# P04_Power_Supply1.net
KiCad netlist of a schematic drawn in Altium Designer
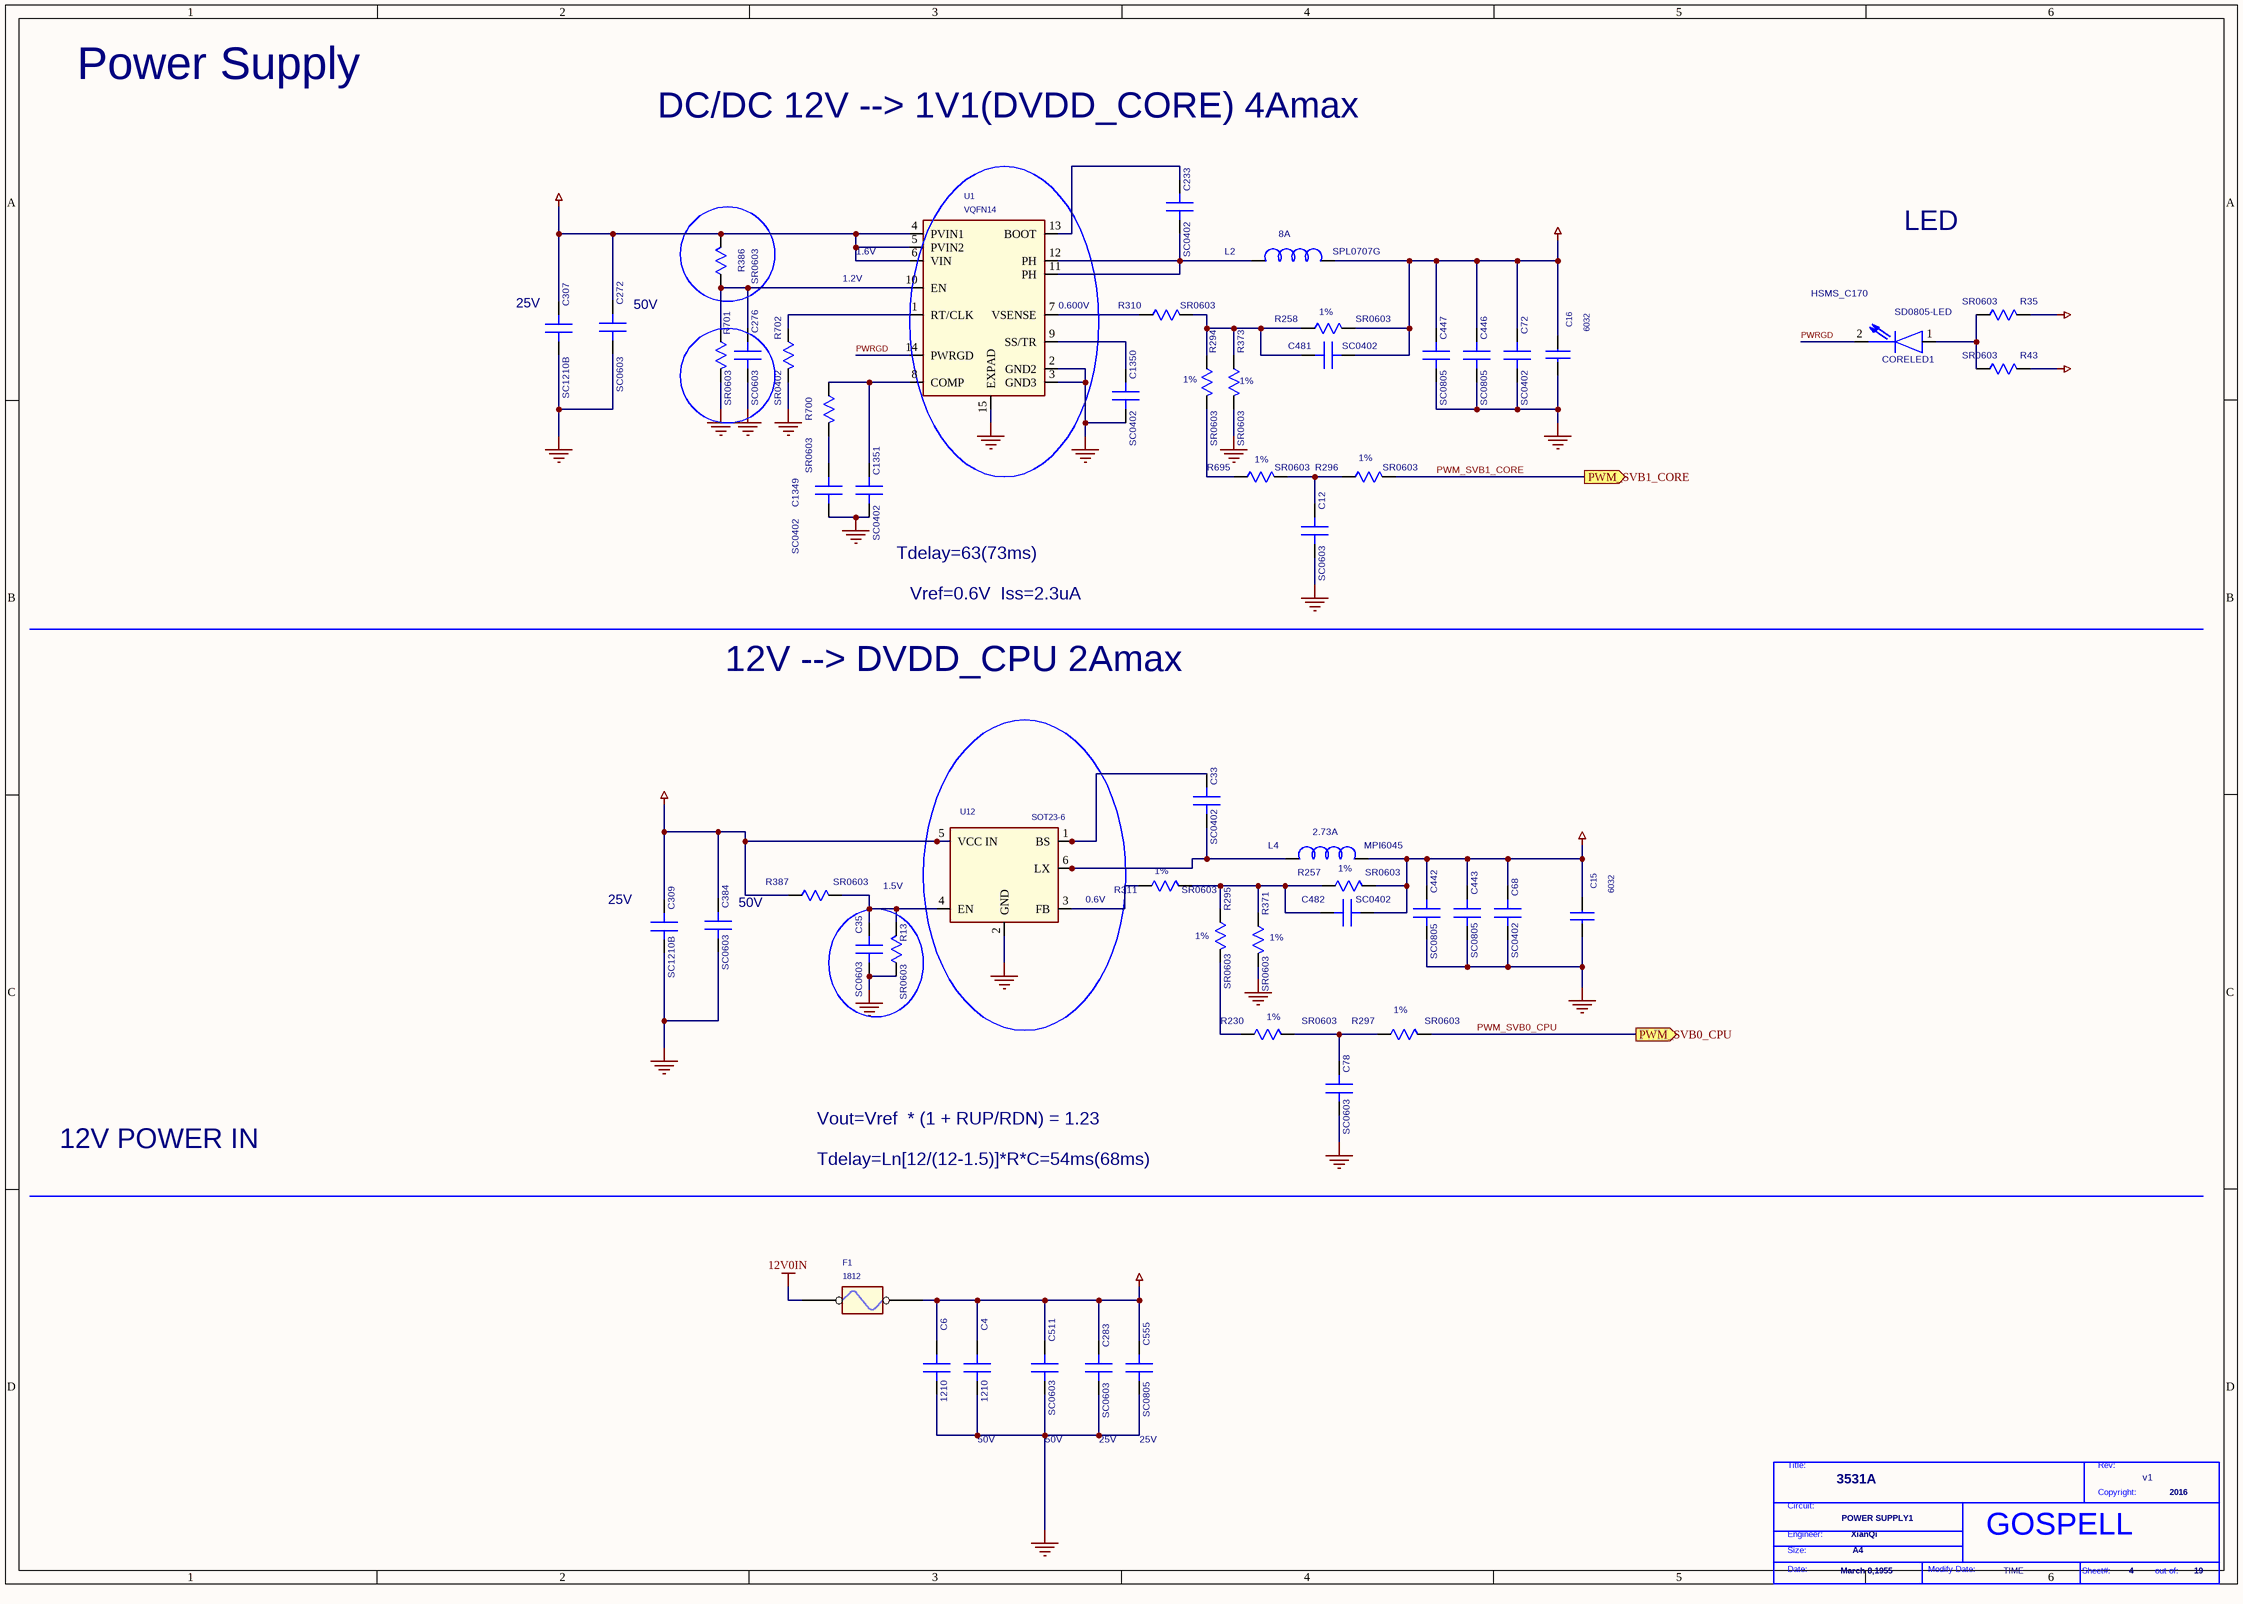
[diagram p0: P04 Power Supply1.SchDoc]

(export (version "E")
  (design (tool "Eeschema 10.0.6"))
  (components
    (comp (ref "C4") (value "1210") (footprint "1210") (libsource (lib "*") (part "C_0_Dup2")))
    (comp (ref "C6") (value "1210") (footprint "1210") (libsource (lib "*") (part "C_0_Dup2")))
    (comp (ref "C12") (value "SC0603") (libsource (lib "*") (part "C_0")))
    (comp (ref "C15") (value "6032") (footprint "6032") (libsource (lib "*") (part "CAP NP")))
    (comp (ref "C16") (value "6032") (footprint "6032") (libsource (lib "*") (part "CAP NP")))
    (comp (ref "C33") (value "SC0402") (libsource (lib "*") (part "C_0_Dup2")))
    (comp (ref "C35") (value "SC0603") (libsource (lib "*") (part "C_0_Dup2")))
    (comp (ref "C68") (value "SC0402") (libsource (lib "*") (part "C_0_Dup2")))
    (comp (ref "C72") (value "SC0402") (libsource (lib "*") (part "C_0")))
    (comp (ref "C78") (value "SC0603") (libsource (lib "*") (part "C_0_Dup2")))
    (comp (ref "C233") (value "SC0402") (libsource (lib "*") (part "C_0")))
    (comp (ref "C272") (value "SC0603") (libsource (lib "*") (part "C_0")))
    (comp (ref "C276") (value "SC0603") (libsource (lib "*") (part "C_0")))
    (comp (ref "C283") (value "SC0603") (libsource (lib "*") (part "C_0_Dup2")))
    (comp (ref "C307") (value "SC1210B") (libsource (lib "*") (part "C_0")))
    (comp (ref "C309") (value "SC1210B") (libsource (lib "*") (part "C_0_Dup2")))
    (comp (ref "C384") (value "SC0603") (libsource (lib "*") (part "C_0_Dup2")))
    (comp (ref "C442") (value "SC0805") (libsource (lib "*") (part "C_0_Dup2")))
    (comp (ref "C443") (value "SC0805") (libsource (lib "*") (part "C_0_Dup2")))
    (comp (ref "C446") (value "SC0805") (libsource (lib "*") (part "C_0")))
    (comp (ref "C447") (value "SC0805") (libsource (lib "*") (part "C_0")))
    (comp (ref "C481") (value "SC0402") (libsource (lib "*") (part "C_0")))
    (comp (ref "C482") (value "SC0402") (libsource (lib "*") (part "C_0_Dup2")))
    (comp (ref "C511") (value "SC0603") (libsource (lib "*") (part "C_0_Dup2")))
    (comp (ref "C555") (value "SC0805") (libsource (lib "*") (part "C_0_Dup2")))
    (comp (ref "C1349") (value "SC0402") (libsource (lib "*") (part "C_0")))
    (comp (ref "C1350") (value "SC0402") (libsource (lib "*") (part "C_0")))
    (comp (ref "C1351") (value "SC0402") (libsource (lib "*") (part "C_0")))
    (comp (ref "CORELED1")
      (value "SD0805-LED")
      (fields (field (name "DEVICE") "HSMS_C170"))
      (libsource (lib "*") (part "LED_1"))
    )
    (comp (ref "F1") (value "1812") (libsource (lib "*") (part "FUSEHOLDER")))
    (comp (ref "L2") (value "SPL0707G") (libsource (lib "*") (part "L_0")))
    (comp (ref "L4") (value "MPI6045") (libsource (lib "*") (part "L_0_Dup1")))
    (comp (ref "R13") (value "SR0603") (libsource (lib "*") (part "R_1")))
    (comp (ref "R35") (value "SR0603") (libsource (lib "*") (part "R_1")))
    (comp (ref "R43") (value "SR0603") (libsource (lib "*") (part "R_1")))
    (comp (ref "R230") (value "SR0603") (libsource (lib "*") (part "R_1")))
    (comp (ref "R257") (value "SR0603") (libsource (lib "*") (part "R_1")))
    (comp (ref "R258") (value "SR0603") (libsource (lib "*") (part "R_0")))
    (comp (ref "R294") (value "SR0603") (libsource (lib "*") (part "R_0")))
    (comp (ref "R295") (value "SR0603") (libsource (lib "*") (part "R_1")))
    (comp (ref "R296") (value "SR0603") (libsource (lib "*") (part "R_0")))
    (comp (ref "R297") (value "SR0603") (libsource (lib "*") (part "R_1")))
    (comp (ref "R310") (value "SR0603") (libsource (lib "*") (part "R_0")))
    (comp (ref "R311") (value "SR0603") (libsource (lib "*") (part "R_1")))
    (comp (ref "R371") (value "SR0603") (libsource (lib "*") (part "R_1")))
    (comp (ref "R373") (value "SR0603") (libsource (lib "*") (part "R_0")))
    (comp (ref "R386") (value "SR0603") (libsource (lib "*") (part "R_0")))
    (comp (ref "R387") (value "SR0603") (libsource (lib "*") (part "R_1")))
    (comp (ref "R695") (value "SR0603") (libsource (lib "*") (part "R_0")))
    (comp (ref "R700") (value "SR0603") (libsource (lib "*") (part "R_0")))
    (comp (ref "R701") (value "SR0603") (libsource (lib "*") (part "R_0")))
    (comp (ref "R702") (value "SR0402") (libsource (lib "*") (part "R_0")))
    (comp (ref "U1") (value "VQFN14") (footprint "VQFN14") (libsource (lib "*") (part "TPS54821")))
    (comp (ref "U12") (value "SOT23-6") (footprint "SOT23-6") (libsource (lib "*") (part "SY8120")))
  )
  (nets
    (net (code "1") (name "/PWM_SVB0_CPU") (class "Default")
      (node (ref "R297") (pin "2") (pinfunction "B_2") (pintype "passive"))
    )
    (net (code "2") (name "/PWM_SVB1_CORE") (class "Default")
      (node (ref "R296") (pin "2") (pinfunction "B_2") (pintype "passive"))
    )
    (net (code "3") (name "/PWRGD") (class "Default")
      (node (ref "CORELED1") (pin "2") (pinfunction "B_2") (pintype "passive"))
      (node (ref "U1") (pin "14") (pinfunction "PWRGD_14") (pintype "passive"))
    )
    (net (code "4") (name "3V3") (class "Default")
      (node (ref "R35") (pin "1") (pinfunction "A_1") (pintype "passive"))
    )
    (net (code "5") (name "12V0") (class "Default")
      (node (ref "C272") (pin "1") (pinfunction "A_1") (pintype "passive"))
      (node (ref "C283") (pin "1") (pinfunction "A_1") (pintype "passive"))
      (node (ref "C307") (pin "1") (pinfunction "A_1") (pintype "passive"))
      (node (ref "C309") (pin "1") (pinfunction "A_1") (pintype "passive"))
      (node (ref "C384") (pin "1") (pinfunction "A_1") (pintype "passive"))
      (node (ref "C4") (pin "1") (pinfunction "A_1") (pintype "passive"))
      (node (ref "C511") (pin "1") (pinfunction "A_1") (pintype "passive"))
      (node (ref "C555") (pin "1") (pinfunction "A_1") (pintype "passive"))
      (node (ref "C6") (pin "1") (pinfunction "A_1") (pintype "passive"))
      (node (ref "F1") (pin "2") (pinfunction "2_2") (pintype "passive"))
      (node (ref "R386") (pin "2") (pinfunction "B_2") (pintype "passive"))
      (node (ref "R387") (pin "1") (pinfunction "A_1") (pintype "passive"))
      (node (ref "R43") (pin "1") (pinfunction "A_1") (pintype "passive"))
      (node (ref "U1") (pin "4") (pinfunction "PVIN1_4") (pintype "passive"))
      (node (ref "U1") (pin "5") (pinfunction "PVIN2_5") (pintype "passive"))
      (node (ref "U1") (pin "6") (pinfunction "VIN_6") (pintype "passive"))
      (node (ref "U12") (pin "5") (pinfunction "VCC_IN_5") (pintype "passive"))
    )
    (net (code "6") (name "12V0IN") (class "Default")
      (node (ref "F1") (pin "1") (pinfunction "1_1") (pintype "passive"))
    )
    (net (code "7") (name "DVDD_CORE") (class "Default")
      (node (ref "C16") (pin "1") (pinfunction "1_1") (pintype "passive"))
      (node (ref "C446") (pin "1") (pinfunction "A_1") (pintype "passive"))
      (node (ref "C447") (pin "1") (pinfunction "A_1") (pintype "passive"))
      (node (ref "C481") (pin "2") (pinfunction "B_2") (pintype "passive"))
      (node (ref "C72") (pin "1") (pinfunction "A_1") (pintype "passive"))
      (node (ref "L2") (pin "2") (pinfunction "B_2") (pintype "passive"))
      (node (ref "R258") (pin "2") (pinfunction "B_2") (pintype "passive"))
    )
    (net (code "8") (name "DVDD_CPU") (class "Default")
      (node (ref "C15") (pin "1") (pinfunction "1_1") (pintype "passive"))
      (node (ref "C442") (pin "1") (pinfunction "A_1") (pintype "passive"))
      (node (ref "C443") (pin "1") (pinfunction "A_1") (pintype "passive"))
      (node (ref "C482") (pin "2") (pinfunction "B_2") (pintype "passive"))
      (node (ref "C68") (pin "1") (pinfunction "A_1") (pintype "passive"))
      (node (ref "L4") (pin "2") (pinfunction "B_2") (pintype "passive"))
      (node (ref "R257") (pin "2") (pinfunction "B_2") (pintype "passive"))
    )
    (net (code "9") (name "GND") (class "Default")
      (node (ref "C12") (pin "2") (pinfunction "B_2") (pintype "passive"))
      (node (ref "C1349") (pin "2") (pinfunction "B_2") (pintype "passive"))
      (node (ref "C1350") (pin "2") (pinfunction "B_2") (pintype "passive"))
      (node (ref "C1351") (pin "2") (pinfunction "B_2") (pintype "passive"))
      (node (ref "C15") (pin "2") (pinfunction "2_2") (pintype "passive"))
      (node (ref "C16") (pin "2") (pinfunction "2_2") (pintype "passive"))
      (node (ref "C272") (pin "2") (pinfunction "B_2") (pintype "passive"))
      (node (ref "C276") (pin "2") (pinfunction "B_2") (pintype "passive"))
      (node (ref "C283") (pin "2") (pinfunction "B_2") (pintype "passive"))
      (node (ref "C307") (pin "2") (pinfunction "B_2") (pintype "passive"))
      (node (ref "C309") (pin "2") (pinfunction "B_2") (pintype "passive"))
      (node (ref "C35") (pin "2") (pinfunction "B_2") (pintype "passive"))
      (node (ref "C384") (pin "2") (pinfunction "B_2") (pintype "passive"))
      (node (ref "C4") (pin "2") (pinfunction "B_2") (pintype "passive"))
      (node (ref "C442") (pin "2") (pinfunction "B_2") (pintype "passive"))
      (node (ref "C443") (pin "2") (pinfunction "B_2") (pintype "passive"))
      (node (ref "C446") (pin "2") (pinfunction "B_2") (pintype "passive"))
      (node (ref "C447") (pin "2") (pinfunction "B_2") (pintype "passive"))
      (node (ref "C511") (pin "2") (pinfunction "B_2") (pintype "passive"))
      (node (ref "C555") (pin "2") (pinfunction "B_2") (pintype "passive"))
      (node (ref "C6") (pin "2") (pinfunction "B_2") (pintype "passive"))
      (node (ref "C68") (pin "2") (pinfunction "B_2") (pintype "passive"))
      (node (ref "C72") (pin "2") (pinfunction "B_2") (pintype "passive"))
      (node (ref "C78") (pin "2") (pinfunction "B_2") (pintype "passive"))
      (node (ref "R13") (pin "1") (pinfunction "A_1") (pintype "passive"))
      (node (ref "R371") (pin "2") (pinfunction "B_2") (pintype "passive"))
      (node (ref "R373") (pin "2") (pinfunction "B_2") (pintype "passive"))
      (node (ref "R701") (pin "2") (pinfunction "B_2") (pintype "passive"))
      (node (ref "R702") (pin "2") (pinfunction "B_2") (pintype "passive"))
      (node (ref "U1") (pin "15") (pinfunction "EXPAD_15") (pintype "passive"))
      (node (ref "U1") (pin "2") (pinfunction "GND2_2") (pintype "passive"))
      (node (ref "U1") (pin "3") (pinfunction "GND3_3") (pintype "passive"))
      (node (ref "U12") (pin "2") (pinfunction "GND_2") (pintype "passive"))
    )
    (net (code "10") (name "Net-(C12-A)") (class "Default")
      (node (ref "C12") (pin "1") (pinfunction "A_1") (pintype "passive"))
      (node (ref "R296") (pin "1") (pinfunction "A_1") (pintype "passive"))
      (node (ref "R695") (pin "2") (pinfunction "B_2") (pintype "passive"))
    )
    (net (code "11") (name "Net-(C33-A)") (class "Default")
      (node (ref "C33") (pin "1") (pinfunction "A_1") (pintype "passive"))
      (node (ref "U12") (pin "1") (pinfunction "BS_1") (pintype "passive"))
    )
    (net (code "12") (name "Net-(C33-B)") (class "Default")
      (node (ref "C33") (pin "2") (pinfunction "B_2") (pintype "passive"))
      (node (ref "L4") (pin "1") (pinfunction "A_1") (pintype "passive"))
      (node (ref "U12") (pin "6") (pinfunction "LX_6") (pintype "passive"))
    )
    (net (code "13") (name "Net-(C35-A)") (class "Default")
      (node (ref "C35") (pin "1") (pinfunction "A_1") (pintype "passive"))
      (node (ref "R13") (pin "2") (pinfunction "B_2") (pintype "passive"))
      (node (ref "R387") (pin "2") (pinfunction "B_2") (pintype "passive"))
      (node (ref "U12") (pin "4") (pinfunction "EN_4") (pintype "passive"))
    )
    (net (code "14") (name "Net-(C78-A)") (class "Default")
      (node (ref "C78") (pin "1") (pinfunction "A_1") (pintype "passive"))
      (node (ref "R230") (pin "2") (pinfunction "B_2") (pintype "passive"))
      (node (ref "R297") (pin "1") (pinfunction "A_1") (pintype "passive"))
    )
    (net (code "15") (name "Net-(C233-A)") (class "Default")
      (node (ref "C233") (pin "1") (pinfunction "A_1") (pintype "passive"))
      (node (ref "U1") (pin "13") (pinfunction "BOOT_13") (pintype "passive"))
    )
    (net (code "16") (name "Net-(C233-B)") (class "Default")
      (node (ref "C233") (pin "2") (pinfunction "B_2") (pintype "passive"))
      (node (ref "L2") (pin "1") (pinfunction "A_1") (pintype "passive"))
      (node (ref "U1") (pin "11") (pinfunction "PH_11") (pintype "passive"))
      (node (ref "U1") (pin "12") (pinfunction "PH_12") (pintype "passive"))
    )
    (net (code "17") (name "Net-(C276-A)") (class "Default")
      (node (ref "C276") (pin "1") (pinfunction "A_1") (pintype "passive"))
      (node (ref "R386") (pin "1") (pinfunction "A_1") (pintype "passive"))
      (node (ref "R701") (pin "1") (pinfunction "A_1") (pintype "passive"))
      (node (ref "U1") (pin "10") (pinfunction "EN_10") (pintype "passive"))
    )
    (net (code "18") (name "Net-(C481-A)") (class "Default")
      (node (ref "C481") (pin "1") (pinfunction "A_1") (pintype "passive"))
      (node (ref "R258") (pin "1") (pinfunction "A_1") (pintype "passive"))
      (node (ref "R294") (pin "1") (pinfunction "A_1") (pintype "passive"))
      (node (ref "R310") (pin "2") (pinfunction "B_2") (pintype "passive"))
      (node (ref "R373") (pin "1") (pinfunction "A_1") (pintype "passive"))
    )
    (net (code "19") (name "Net-(C482-A)") (class "Default")
      (node (ref "C482") (pin "1") (pinfunction "A_1") (pintype "passive"))
      (node (ref "R257") (pin "1") (pinfunction "A_1") (pintype "passive"))
      (node (ref "R295") (pin "1") (pinfunction "A_1") (pintype "passive"))
      (node (ref "R311") (pin "2") (pinfunction "B_2") (pintype "passive"))
      (node (ref "R371") (pin "1") (pinfunction "A_1") (pintype "passive"))
    )
    (net (code "20") (name "Net-(C1349-A)") (class "Default")
      (node (ref "C1349") (pin "1") (pinfunction "A_1") (pintype "passive"))
      (node (ref "R700") (pin "2") (pinfunction "B_2") (pintype "passive"))
    )
    (net (code "21") (name "Net-(C1350-A)") (class "Default")
      (node (ref "C1350") (pin "1") (pinfunction "A_1") (pintype "passive"))
      (node (ref "U1") (pin "9") (pinfunction "SS/TR_9") (pintype "passive"))
    )
    (net (code "22") (name "Net-(C1351-A)") (class "Default")
      (node (ref "C1351") (pin "1") (pinfunction "A_1") (pintype "passive"))
      (node (ref "R700") (pin "1") (pinfunction "A_1") (pintype "passive"))
      (node (ref "U1") (pin "8") (pinfunction "COMP_8") (pintype "passive"))
    )
    (net (code "23") (name "Net-(CORELED1-A)") (class "Default")
      (node (ref "CORELED1") (pin "1") (pinfunction "A_1") (pintype "passive"))
      (node (ref "R35") (pin "2") (pinfunction "B_2") (pintype "passive"))
      (node (ref "R43") (pin "2") (pinfunction "B_2") (pintype "passive"))
    )
    (net (code "24") (name "Net-(R230-A)") (class "Default")
      (node (ref "R230") (pin "1") (pinfunction "A_1") (pintype "passive"))
      (node (ref "R295") (pin "2") (pinfunction "B_2") (pintype "passive"))
    )
    (net (code "25") (name "Net-(R294-B)") (class "Default")
      (node (ref "R294") (pin "2") (pinfunction "B_2") (pintype "passive"))
      (node (ref "R695") (pin "1") (pinfunction "A_1") (pintype "passive"))
    )
    (net (code "26") (name "Net-(R310-A)") (class "Default")
      (node (ref "R310") (pin "1") (pinfunction "A_1") (pintype "passive"))
      (node (ref "U1") (pin "7") (pinfunction "VSENSE_7") (pintype "passive"))
    )
    (net (code "27") (name "Net-(R311-A)") (class "Default")
      (node (ref "R311") (pin "1") (pinfunction "A_1") (pintype "passive"))
      (node (ref "U12") (pin "3") (pinfunction "FB_3") (pintype "passive"))
    )
    (net (code "28") (name "Net-(R702-A)") (class "Default")
      (node (ref "R702") (pin "1") (pinfunction "A_1") (pintype "passive"))
      (node (ref "U1") (pin "1") (pinfunction "RT/CLK_1") (pintype "passive"))
    )
  )
)
